# main-stm-03_1.net
KiCad netlist of a schematic drawn in EAGLE
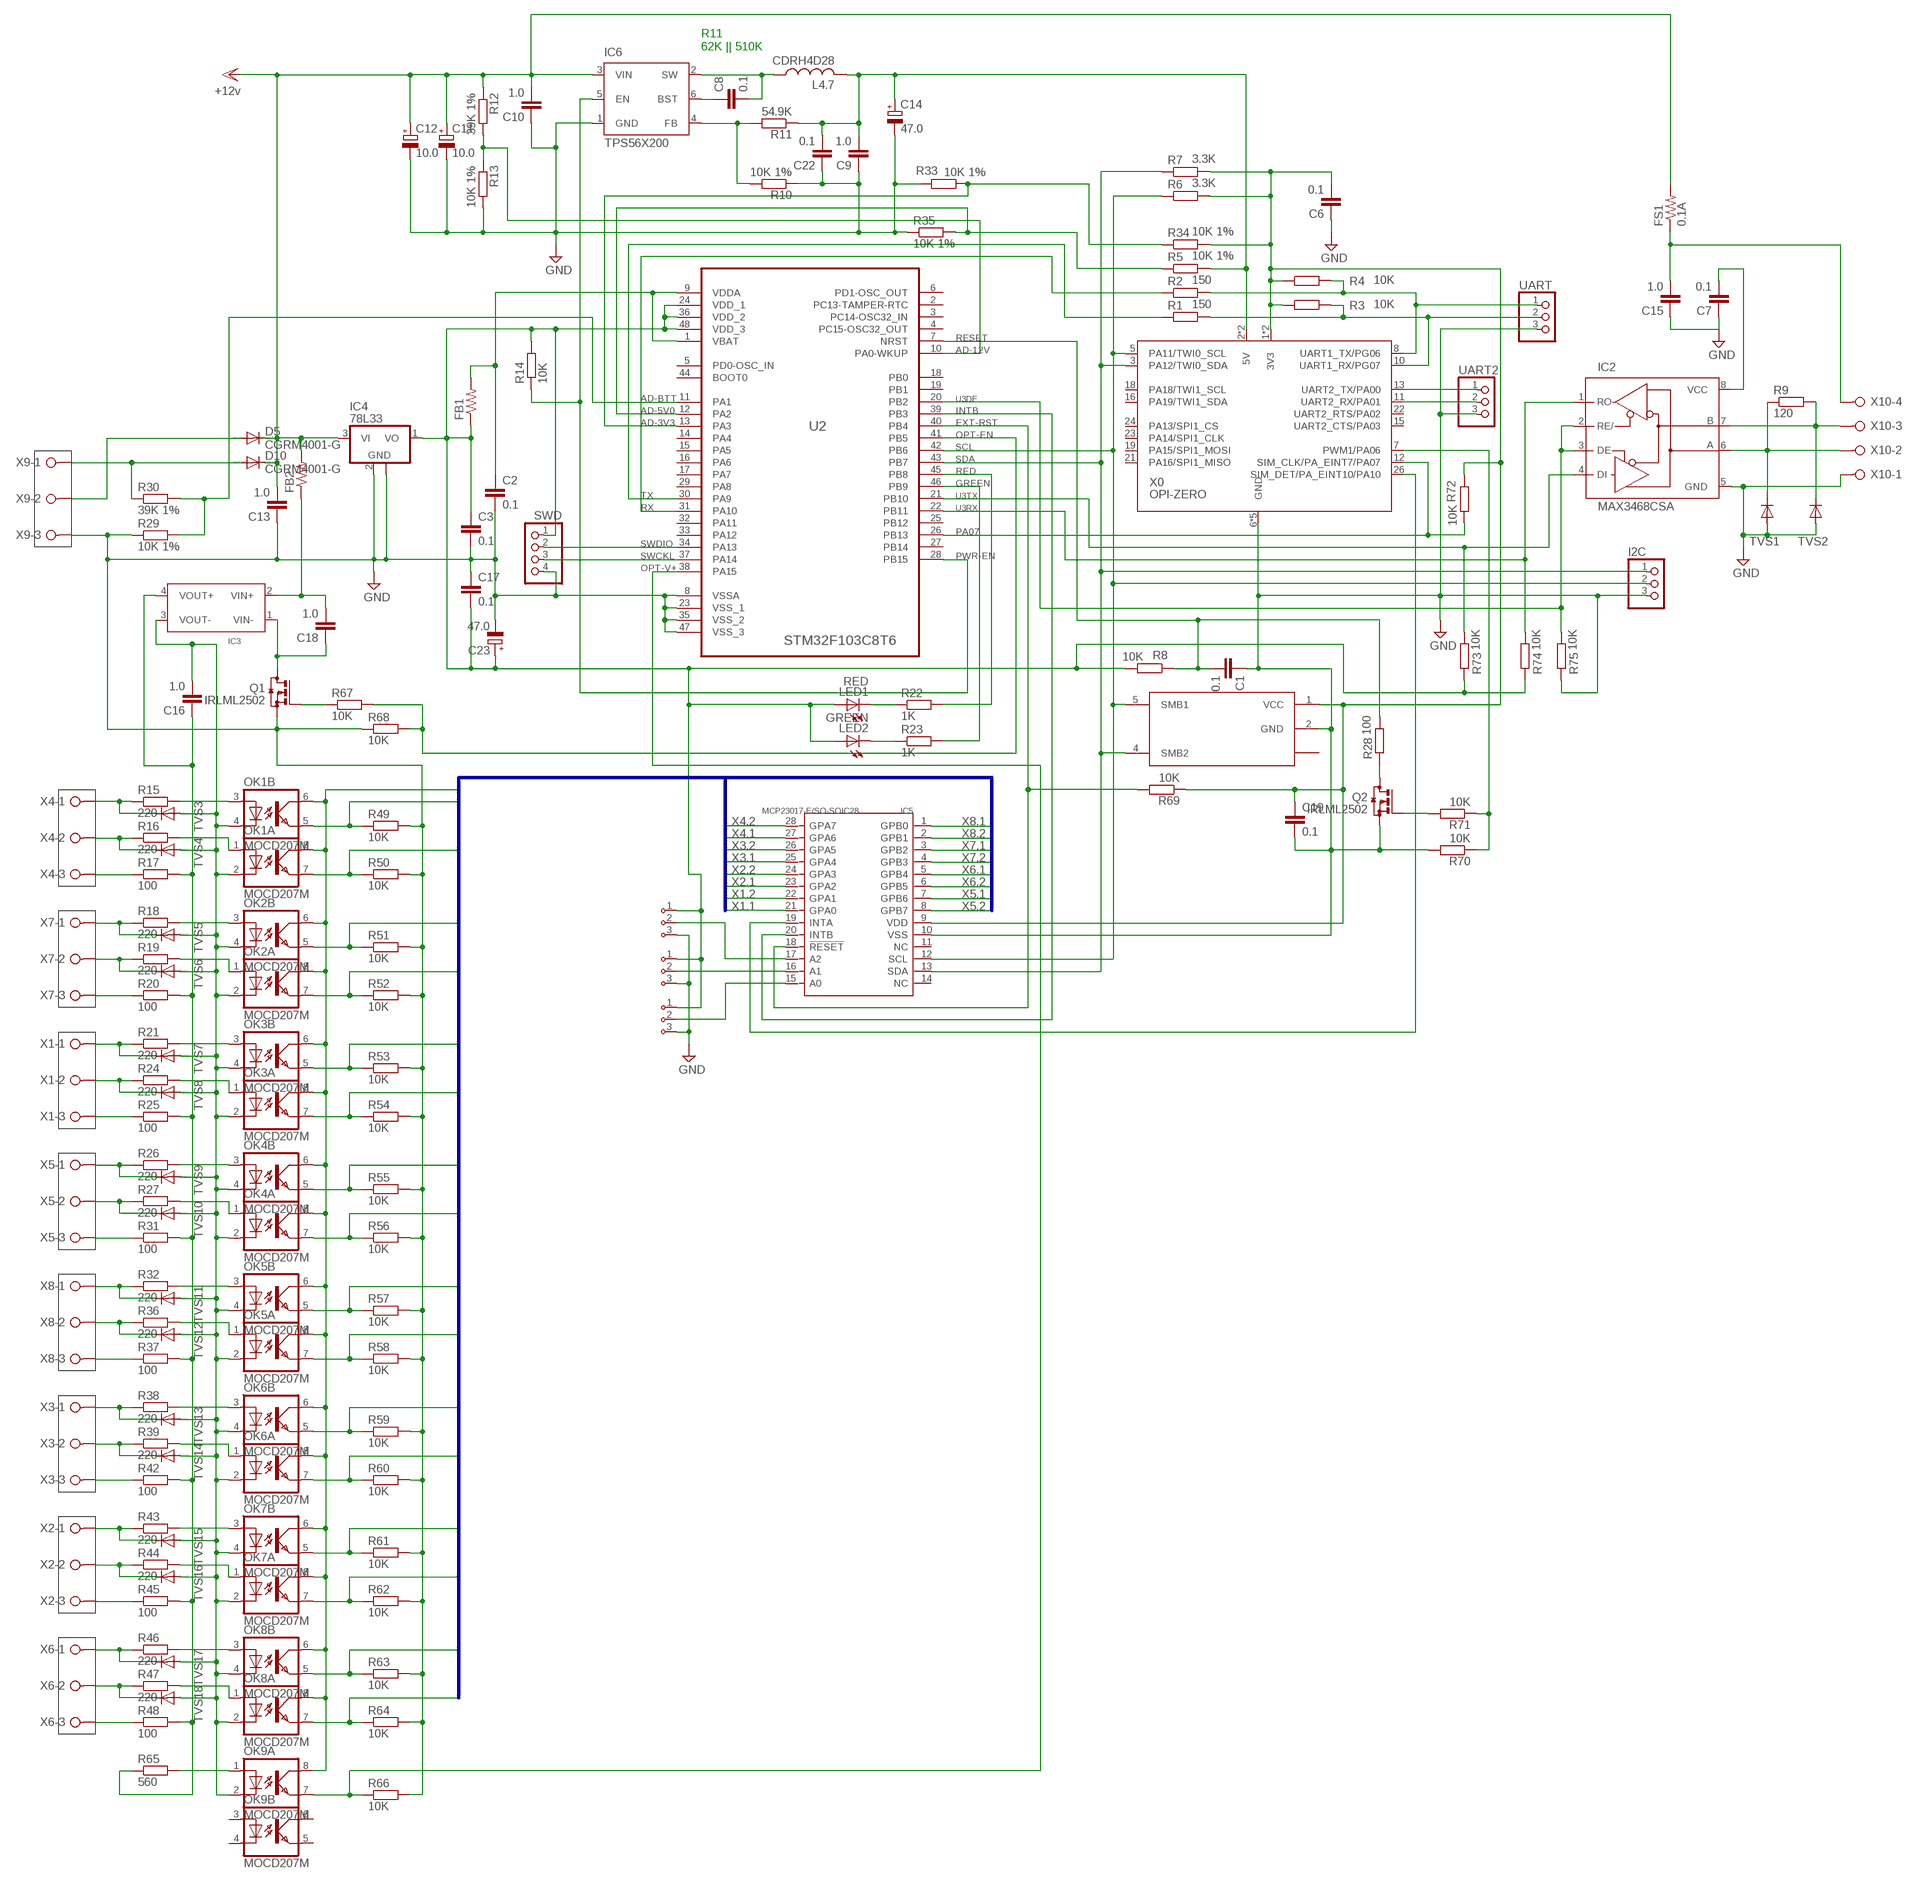
[diagram p0: schematic, sheet 1]

(export (version "E")
  (design (tool "Eeschema 10.0.6"))
  (components
    (comp (ref "A0")
      (value "ADDR3PIN0603")
      (footprint "eagle-import:0603-3PIN")
      (libsource (lib "eagle-import") (part "ADDR3PIN0603"))
    )
    (comp (ref "A1")
      (value "ADDR3PIN0603")
      (footprint "eagle-import:0603-3PIN")
      (libsource (lib "eagle-import") (part "ADDR3PIN0603"))
    )
    (comp (ref "A2")
      (value "ADDR3PIN0603")
      (footprint "eagle-import:0603-3PIN")
      (libsource (lib "eagle-import") (part "ADDR3PIN0603"))
    )
    (comp (ref "C1")
      (value "0.1")
      (footprint "eagle-import:C0603")
      (libsource (lib "eagle-import") (part "C-EUC0603"))
    )
    (comp (ref "C2")
      (value "0.1")
      (footprint "eagle-import:C0603")
      (libsource (lib "eagle-import") (part "C-EUC0603"))
    )
    (comp (ref "C3")
      (value "0.1")
      (footprint "eagle-import:C0603")
      (libsource (lib "eagle-import") (part "C-EUC0603"))
    )
    (comp (ref "C6")
      (value "0.1")
      (footprint "eagle-import:C0805")
      (libsource (lib "eagle-import") (part "C-EUC0805"))
    )
    (comp (ref "C7")
      (value "0.1")
      (footprint "eagle-import:C0805")
      (libsource (lib "eagle-import") (part "C-EUC0805"))
    )
    (comp (ref "C8")
      (value "0.1")
      (footprint "eagle-import:C0805")
      (libsource (lib "eagle-import") (part "C-EUC0805"))
    )
    (comp (ref "C9")
      (value "1.0")
      (footprint "eagle-import:C0805")
      (libsource (lib "eagle-import") (part "C-EUC0805"))
    )
    (comp (ref "C10")
      (value "1.0")
      (footprint "eagle-import:C1206")
      (libsource (lib "eagle-import") (part "C-EUC1206"))
    )
    (comp (ref "C11")
      (value "10.0")
      (footprint "eagle-import:C_6032-28R")
      (libsource (lib "eagle-import") (part "CPOL-EUC/6032-28R"))
    )
    (comp (ref "C12")
      (value "10.0")
      (footprint "eagle-import:C_6032-28R")
      (libsource (lib "eagle-import") (part "CPOL-EUC/6032-28R"))
    )
    (comp (ref "C13")
      (value "1.0")
      (footprint "eagle-import:C1206")
      (libsource (lib "eagle-import") (part "C-EUC1206"))
    )
    (comp (ref "C14")
      (value "47.0")
      (footprint "eagle-import:B_3528-21R")
      (libsource (lib "eagle-import") (part "CPOL-EUB/3528-21R"))
    )
    (comp (ref "C15")
      (value "1.0")
      (footprint "eagle-import:C1206")
      (libsource (lib "eagle-import") (part "C-EUC1206"))
    )
    (comp (ref "C16")
      (value "1.0")
      (footprint "eagle-import:C1206")
      (libsource (lib "eagle-import") (part "C-EUC1206"))
    )
    (comp (ref "C17")
      (value "0.1")
      (footprint "eagle-import:C0603")
      (libsource (lib "eagle-import") (part "C-EUC0603"))
    )
    (comp (ref "C18")
      (value "1.0")
      (footprint "eagle-import:C1206")
      (libsource (lib "eagle-import") (part "C-EUC1206"))
    )
    (comp (ref "C19")
      (value "0.1")
      (footprint "eagle-import:C0603")
      (libsource (lib "eagle-import") (part "C-EUC0603"))
    )
    (comp (ref "C22")
      (value "0.1")
      (footprint "eagle-import:C0805")
      (libsource (lib "eagle-import") (part "C-EUC0805"))
    )
    (comp (ref "C23")
      (value "47.0")
      (footprint "eagle-import:B_3528-21R")
      (libsource (lib "eagle-import") (part "CPOL-EUB/3528-21R"))
    )
    (comp (ref "D5")
      (value "CGRM4001-G")
      (footprint "eagle-import:SOD-123_MINI-SMA")
      (libsource (lib "eagle-import") (part "CGRM400-G1"))
    )
    (comp (ref "D10")
      (value "CGRM4001-G")
      (footprint "eagle-import:SOD-123_MINI-SMA")
      (libsource (lib "eagle-import") (part "CGRM400-G1"))
    )
    (comp (ref "FB1")
      (value "R-US_R0805")
      (footprint "eagle-import:R0805")
      (libsource (lib "eagle-import") (part "R-US_R0805"))
    )
    (comp (ref "FB2")
      (value "R-US_R1206")
      (footprint "eagle-import:R1206")
      (libsource (lib "eagle-import") (part "R-US_R1206"))
    )
    (comp (ref "FS1")
      (value "0.1A")
      (footprint "eagle-import:R1210")
      (libsource (lib "eagle-import") (part "R-US_R1210"))
    )
    (comp (ref "I2C")
      (value "PINHD-1X3")
      (footprint "eagle-import:1X03")
      (libsource (lib "eagle-import") (part "PINHD-1X3"))
    )
    (comp (ref "IC2")
      (value "MAX3468CSA")
      (footprint "eagle-import:SO08")
      (fields (field (name "MPN") "MAX3468CSA+"))
      (libsource (lib "eagle-import") (part "MAX34SA68C"))
    )
    (comp (ref "IC3")
      (value "DC-DC-CONV-4PIN-ISOLATINGMURATA-NME-05-12-SERIES")
      (footprint "eagle-import:DC-DC-MURATA-NME-05-12-SERIES")
      (libsource (lib "eagle-import") (part "DC-DC-CONV-4PIN-ISOLATINGMURATA-NME-05-12-SERIES"))
    )
    (comp (ref "IC4")
      (value "78L33")
      (footprint "eagle-import:SOT89")
      (libsource (lib "eagle-import") (part "78LF05"))
    )
    (comp (ref "IC5")
      (value "MCP23017-E/SO-SOIC28")
      (footprint "eagle-import:SOIC28-1.27-17.9X7.5MM")
      (fields (field (name "MPN") "MCP23017-E/SO"))
      (libsource (lib "eagle-import") (part "INTERFACE-MCP23017-E(SOIC28)"))
    )
    (comp (ref "IC6")
      (value "TPS56X200")
      (footprint "eagle-import:TSOT23-6_DDC")
      (libsource (lib "eagle-import") (part "TPS56X200"))
    )
    (comp (ref "IC7")
      (value "LTC1694")
      (footprint "eagle-import:SOT23-5")
      (libsource (lib "eagle-import") (part "LTC1694"))
    )
    (comp (ref "L4.7")
      (value "CDRH4D28")
      (footprint "eagle-import:CDRH4D28")
      (libsource (lib "eagle-import") (part "CDRH4D28"))
    )
    (comp (ref "LED1")
      (value "RED")
      (footprint "eagle-import:CHIPLED_1206")
      (libsource (lib "eagle-import") (part "LEDCHIPLED_1206"))
    )
    (comp (ref "LED2")
      (value "GREEN")
      (footprint "eagle-import:CHIPLED_1206")
      (libsource (lib "eagle-import") (part "LEDCHIPLED_1206"))
    )
    (comp (ref "OK1")
      (value "MOCD207M")
      (footprint "eagle-import:SOIC08-FAIRCHILD")
      (fields (field (name "MF") "FAIRCHILD SEMICONDUCTOR") (field (name "MPN") "MOCD207-M"))
      (libsource (lib "eagle-import") (part "MOCD20M7"))
    )
    (comp (ref "OK2")
      (value "MOCD207M")
      (footprint "eagle-import:SOIC08-FAIRCHILD")
      (fields (field (name "MF") "FAIRCHILD SEMICONDUCTOR") (field (name "MPN") "MOCD207-M"))
      (libsource (lib "eagle-import") (part "MOCD20M7"))
    )
    (comp (ref "OK3")
      (value "MOCD207M")
      (footprint "eagle-import:SOIC08-FAIRCHILD")
      (fields (field (name "MF") "FAIRCHILD SEMICONDUCTOR") (field (name "MPN") "MOCD207-M"))
      (libsource (lib "eagle-import") (part "MOCD20M7"))
    )
    (comp (ref "OK4")
      (value "MOCD207M")
      (footprint "eagle-import:SOIC08-FAIRCHILD")
      (fields (field (name "MF") "FAIRCHILD SEMICONDUCTOR") (field (name "MPN") "MOCD207-M"))
      (libsource (lib "eagle-import") (part "MOCD20M7"))
    )
    (comp (ref "OK5")
      (value "MOCD207M")
      (footprint "eagle-import:SOIC08-FAIRCHILD")
      (fields (field (name "MF") "FAIRCHILD SEMICONDUCTOR") (field (name "MPN") "MOCD207-M"))
      (libsource (lib "eagle-import") (part "MOCD20M7"))
    )
    (comp (ref "OK6")
      (value "MOCD207M")
      (footprint "eagle-import:SOIC08-FAIRCHILD")
      (fields (field (name "MF") "FAIRCHILD SEMICONDUCTOR") (field (name "MPN") "MOCD207-M"))
      (libsource (lib "eagle-import") (part "MOCD20M7"))
    )
    (comp (ref "OK7")
      (value "MOCD207M")
      (footprint "eagle-import:SOIC08-FAIRCHILD")
      (fields (field (name "MF") "FAIRCHILD SEMICONDUCTOR") (field (name "MPN") "MOCD207-M"))
      (libsource (lib "eagle-import") (part "MOCD20M7"))
    )
    (comp (ref "OK8")
      (value "MOCD207M")
      (footprint "eagle-import:SOIC08-FAIRCHILD")
      (fields (field (name "MF") "FAIRCHILD SEMICONDUCTOR") (field (name "MPN") "MOCD207-M"))
      (libsource (lib "eagle-import") (part "MOCD20M7"))
    )
    (comp (ref "OK9")
      (value "MOCD207M")
      (footprint "eagle-import:SOIC08-FAIRCHILD")
      (fields (field (name "MF") "FAIRCHILD SEMICONDUCTOR") (field (name "MPN") "MOCD207-M"))
      (libsource (lib "eagle-import") (part "MOCD20M7"))
    )
    (comp (ref "Q1")
      (value "IRLML2502")
      (footprint "eagle-import:SOT23")
      (libsource (lib "eagle-import") (part "IRLML2502"))
    )
    (comp (ref "Q2")
      (value "IRLML2502")
      (footprint "eagle-import:SOT23")
      (libsource (lib "eagle-import") (part "IRLML2502"))
    )
    (comp (ref "R1")
      (value "150")
      (footprint "eagle-import:R0603")
      (libsource (lib "eagle-import") (part "R-EU_R0603"))
    )
    (comp (ref "R2")
      (value "150")
      (footprint "eagle-import:R0603")
      (libsource (lib "eagle-import") (part "R-EU_R0603"))
    )
    (comp (ref "R3")
      (value "10K")
      (footprint "eagle-import:R0603")
      (libsource (lib "eagle-import") (part "R-EU_R0603"))
    )
    (comp (ref "R4")
      (value "10K")
      (footprint "eagle-import:R0603")
      (libsource (lib "eagle-import") (part "R-EU_R0603"))
    )
    (comp (ref "R5")
      (value "10K 1%")
      (footprint "eagle-import:R0603")
      (libsource (lib "eagle-import") (part "R-EU_R0603"))
    )
    (comp (ref "R6")
      (value "3.3K")
      (footprint "eagle-import:R0603")
      (libsource (lib "eagle-import") (part "R-EU_R0603"))
    )
    (comp (ref "R7")
      (value "3.3K")
      (footprint "eagle-import:R0603")
      (libsource (lib "eagle-import") (part "R-EU_R0603"))
    )
    (comp (ref "R8")
      (value "10K")
      (footprint "eagle-import:R0603")
      (libsource (lib "eagle-import") (part "R-EU_R0603"))
    )
    (comp (ref "R9")
      (value "120")
      (footprint "eagle-import:R1206")
      (libsource (lib "eagle-import") (part "R-EU_R1206"))
    )
    (comp (ref "R10")
      (value "10K 1%")
      (footprint "eagle-import:R0603")
      (libsource (lib "eagle-import") (part "R-EU_R0603"))
    )
    (comp (ref "R11")
      (value "54.9K")
      (footprint "eagle-import:R0603")
      (libsource (lib "eagle-import") (part "R-EU_R0603"))
    )
    (comp (ref "R12")
      (value "39K 1%")
      (footprint "eagle-import:R0603")
      (libsource (lib "eagle-import") (part "R-EU_R0603"))
    )
    (comp (ref "R13")
      (value "10K 1%")
      (footprint "eagle-import:R0603")
      (libsource (lib "eagle-import") (part "R-EU_R0603"))
    )
    (comp (ref "R14")
      (value "10K")
      (footprint "eagle-import:R0603")
      (libsource (lib "eagle-import") (part "R-EU_R0603"))
    )
    (comp (ref "R15")
      (value "220")
      (footprint "eagle-import:R0603")
      (libsource (lib "eagle-import") (part "R-EU_R0603"))
    )
    (comp (ref "R16")
      (value "220")
      (footprint "eagle-import:R0603")
      (libsource (lib "eagle-import") (part "R-EU_R0603"))
    )
    (comp (ref "R17")
      (value "100")
      (footprint "eagle-import:R0603")
      (libsource (lib "eagle-import") (part "R-EU_R0603"))
    )
    (comp (ref "R18")
      (value "220")
      (footprint "eagle-import:R0603")
      (libsource (lib "eagle-import") (part "R-EU_R0603"))
    )
    (comp (ref "R19")
      (value "220")
      (footprint "eagle-import:R0603")
      (libsource (lib "eagle-import") (part "R-EU_R0603"))
    )
    (comp (ref "R20")
      (value "100")
      (footprint "eagle-import:R0603")
      (libsource (lib "eagle-import") (part "R-EU_R0603"))
    )
    (comp (ref "R21")
      (value "220")
      (footprint "eagle-import:R0603")
      (libsource (lib "eagle-import") (part "R-EU_R0603"))
    )
    (comp (ref "R22")
      (value "1K")
      (footprint "eagle-import:R0603")
      (libsource (lib "eagle-import") (part "R-EU_R0603"))
    )
    (comp (ref "R23")
      (value "1K")
      (footprint "eagle-import:R0603")
      (libsource (lib "eagle-import") (part "R-EU_R0603"))
    )
    (comp (ref "R24")
      (value "220")
      (footprint "eagle-import:R0603")
      (libsource (lib "eagle-import") (part "R-EU_R0603"))
    )
    (comp (ref "R25")
      (value "100")
      (footprint "eagle-import:R0603")
      (libsource (lib "eagle-import") (part "R-EU_R0603"))
    )
    (comp (ref "R26")
      (value "220")
      (footprint "eagle-import:R0603")
      (libsource (lib "eagle-import") (part "R-EU_R0603"))
    )
    (comp (ref "R27")
      (value "220")
      (footprint "eagle-import:R0603")
      (libsource (lib "eagle-import") (part "R-EU_R0603"))
    )
    (comp (ref "R28")
      (value "100")
      (footprint "eagle-import:R0603")
      (libsource (lib "eagle-import") (part "R-EU_R0603"))
    )
    (comp (ref "R29")
      (value "10K 1%")
      (footprint "eagle-import:R0603")
      (libsource (lib "eagle-import") (part "R-EU_R0603"))
    )
    (comp (ref "R30")
      (value "39K 1%")
      (footprint "eagle-import:R0603")
      (libsource (lib "eagle-import") (part "R-EU_R0603"))
    )
    (comp (ref "R31")
      (value "100")
      (footprint "eagle-import:R0603")
      (libsource (lib "eagle-import") (part "R-EU_R0603"))
    )
    (comp (ref "R32")
      (value "220")
      (footprint "eagle-import:R0603")
      (libsource (lib "eagle-import") (part "R-EU_R0603"))
    )
    (comp (ref "R33")
      (value "10K 1%")
      (footprint "eagle-import:R0603")
      (libsource (lib "eagle-import") (part "R-EU_R0603"))
    )
    (comp (ref "R34")
      (value "10K 1%")
      (footprint "eagle-import:R0603")
      (libsource (lib "eagle-import") (part "R-EU_R0603"))
    )
    (comp (ref "R35")
      (value "10K 1%")
      (footprint "eagle-import:R0603")
      (libsource (lib "eagle-import") (part "R-EU_R0603"))
    )
    (comp (ref "R36")
      (value "220")
      (footprint "eagle-import:R0603")
      (libsource (lib "eagle-import") (part "R-EU_R0603"))
    )
    (comp (ref "R37")
      (value "100")
      (footprint "eagle-import:R0603")
      (libsource (lib "eagle-import") (part "R-EU_R0603"))
    )
    (comp (ref "R38")
      (value "220")
      (footprint "eagle-import:R0603")
      (libsource (lib "eagle-import") (part "R-EU_R0603"))
    )
    (comp (ref "R39")
      (value "220")
      (footprint "eagle-import:R0603")
      (libsource (lib "eagle-import") (part "R-EU_R0603"))
    )
    (comp (ref "R42")
      (value "100")
      (footprint "eagle-import:R0603")
      (libsource (lib "eagle-import") (part "R-EU_R0603"))
    )
    (comp (ref "R43")
      (value "220")
      (footprint "eagle-import:R0603")
      (libsource (lib "eagle-import") (part "R-EU_R0603"))
    )
    (comp (ref "R44")
      (value "220")
      (footprint "eagle-import:R0603")
      (libsource (lib "eagle-import") (part "R-EU_R0603"))
    )
    (comp (ref "R45")
      (value "100")
      (footprint "eagle-import:R0603")
      (libsource (lib "eagle-import") (part "R-EU_R0603"))
    )
    (comp (ref "R46")
      (value "220")
      (footprint "eagle-import:R0603")
      (libsource (lib "eagle-import") (part "R-EU_R0603"))
    )
    (comp (ref "R47")
      (value "220")
      (footprint "eagle-import:R0603")
      (libsource (lib "eagle-import") (part "R-EU_R0603"))
    )
    (comp (ref "R48")
      (value "100")
      (footprint "eagle-import:R0603")
      (libsource (lib "eagle-import") (part "R-EU_R0603"))
    )
    (comp (ref "R49")
      (value "10K")
      (footprint "eagle-import:R0603")
      (libsource (lib "eagle-import") (part "R-EU_R0603"))
    )
    (comp (ref "R50")
      (value "10K")
      (footprint "eagle-import:R0603")
      (libsource (lib "eagle-import") (part "R-EU_R0603"))
    )
    (comp (ref "R51")
      (value "10K")
      (footprint "eagle-import:R0603")
      (libsource (lib "eagle-import") (part "R-EU_R0603"))
    )
    (comp (ref "R52")
      (value "10K")
      (footprint "eagle-import:R0603")
      (libsource (lib "eagle-import") (part "R-EU_R0603"))
    )
    (comp (ref "R53")
      (value "10K")
      (footprint "eagle-import:R0603")
      (libsource (lib "eagle-import") (part "R-EU_R0603"))
    )
    (comp (ref "R54")
      (value "10K")
      (footprint "eagle-import:R0603")
      (libsource (lib "eagle-import") (part "R-EU_R0603"))
    )
    (comp (ref "R55")
      (value "10K")
      (footprint "eagle-import:R0603")
      (libsource (lib "eagle-import") (part "R-EU_R0603"))
    )
    (comp (ref "R56")
      (value "10K")
      (footprint "eagle-import:R0603")
      (libsource (lib "eagle-import") (part "R-EU_R0603"))
    )
    (comp (ref "R57")
      (value "10K")
      (footprint "eagle-import:R0603")
      (libsource (lib "eagle-import") (part "R-EU_R0603"))
    )
    (comp (ref "R58")
      (value "10K")
      (footprint "eagle-import:R0603")
      (libsource (lib "eagle-import") (part "R-EU_R0603"))
    )
    (comp (ref "R59")
      (value "10K")
      (footprint "eagle-import:R0603")
      (libsource (lib "eagle-import") (part "R-EU_R0603"))
    )
    (comp (ref "R60")
      (value "10K")
      (footprint "eagle-import:R0603")
      (libsource (lib "eagle-import") (part "R-EU_R0603"))
    )
    (comp (ref "R61")
      (value "10K")
      (footprint "eagle-import:R0603")
      (libsource (lib "eagle-import") (part "R-EU_R0603"))
    )
    (comp (ref "R62")
      (value "10K")
      (footprint "eagle-import:R0603")
      (libsource (lib "eagle-import") (part "R-EU_R0603"))
    )
    (comp (ref "R63")
      (value "10K")
      (footprint "eagle-import:R0603")
      (libsource (lib "eagle-import") (part "R-EU_R0603"))
    )
    (comp (ref "R64")
      (value "10K")
      (footprint "eagle-import:R0603")
      (libsource (lib "eagle-import") (part "R-EU_R0603"))
    )
    (comp (ref "R65")
      (value "560")
      (footprint "eagle-import:R0603")
      (libsource (lib "eagle-import") (part "R-EU_R0603"))
    )
    (comp (ref "R66")
      (value "10K")
      (footprint "eagle-import:R0603")
      (libsource (lib "eagle-import") (part "R-EU_R0603"))
    )
    (comp (ref "R67")
      (value "10K")
      (footprint "eagle-import:R0603")
      (libsource (lib "eagle-import") (part "R-EU_R0603"))
    )
    (comp (ref "R68")
      (value "10K")
      (footprint "eagle-import:R0603")
      (libsource (lib "eagle-import") (part "R-EU_R0603"))
    )
    (comp (ref "R69")
      (value "10K")
      (footprint "eagle-import:R0603")
      (libsource (lib "eagle-import") (part "R-EU_R0603"))
    )
    (comp (ref "R70")
      (value "10K")
      (footprint "eagle-import:R0603")
      (libsource (lib "eagle-import") (part "R-EU_R0603"))
    )
    (comp (ref "R71")
      (value "10K")
      (footprint "eagle-import:R0603")
      (libsource (lib "eagle-import") (part "R-EU_R0603"))
    )
    (comp (ref "R72")
      (value "10K")
      (footprint "eagle-import:R0603")
      (libsource (lib "eagle-import") (part "R-EU_R0603"))
    )
    (comp (ref "R73")
      (value "10K")
      (footprint "eagle-import:R0603")
      (libsource (lib "eagle-import") (part "R-EU_R0603"))
    )
    (comp (ref "R74")
      (value "10K")
      (footprint "eagle-import:R0603")
      (libsource (lib "eagle-import") (part "R-EU_R0603"))
    )
    (comp (ref "R75")
      (value "10K")
      (footprint "eagle-import:R0603")
      (libsource (lib "eagle-import") (part "R-EU_R0603"))
    )
    (comp (ref "SWD")
      (value "PINHD-1X4")
      (footprint "eagle-import:1X04")
      (libsource (lib "eagle-import") (part "PINHD-1X4"))
    )
    (comp (ref "TVS1")
      (value "DIODE-SOD323-W")
      (footprint "eagle-import:SOD323-W")
      (libsource (lib "eagle-import") (part "DIODE-SOD323-W"))
    )
    (comp (ref "TVS2")
      (value "DIODE-SOD323-W")
      (footprint "eagle-import:SOD323-W")
      (libsource (lib "eagle-import") (part "DIODE-SOD323-W"))
    )
    (comp (ref "TVS3")
      (value "DIODE-SOD323-W")
      (footprint "eagle-import:SOD323-W")
      (libsource (lib "eagle-import") (part "DIODE-SOD323-W"))
    )
    (comp (ref "TVS4")
      (value "DIODE-SOD323-W")
      (footprint "eagle-import:SOD323-W")
      (libsource (lib "eagle-import") (part "DIODE-SOD323-W"))
    )
    (comp (ref "TVS5")
      (value "DIODE-SOD323-W")
      (footprint "eagle-import:SOD323-W")
      (libsource (lib "eagle-import") (part "DIODE-SOD323-W"))
    )
    (comp (ref "TVS6")
      (value "DIODE-SOD323-W")
      (footprint "eagle-import:SOD323-W")
      (libsource (lib "eagle-import") (part "DIODE-SOD323-W"))
    )
    (comp (ref "TVS7")
      (value "DIODE-SOD323-W")
      (footprint "eagle-import:SOD323-W")
      (libsource (lib "eagle-import") (part "DIODE-SOD323-W"))
    )
    (comp (ref "TVS8")
      (value "DIODE-SOD323-W")
      (footprint "eagle-import:SOD323-W")
      (libsource (lib "eagle-import") (part "DIODE-SOD323-W"))
    )
    (comp (ref "TVS9")
      (value "DIODE-SOD323-W")
      (footprint "eagle-import:SOD323-W")
      (libsource (lib "eagle-import") (part "DIODE-SOD323-W"))
    )
    (comp (ref "TVS10")
      (value "DIODE-SOD323-W")
      (footprint "eagle-import:SOD323-W")
      (libsource (lib "eagle-import") (part "DIODE-SOD323-W"))
    )
    (comp (ref "TVS11")
      (value "DIODE-SOD323-W")
      (footprint "eagle-import:SOD323-W")
      (libsource (lib "eagle-import") (part "DIODE-SOD323-W"))
    )
    (comp (ref "TVS12")
      (value "DIODE-SOD323-W")
      (footprint "eagle-import:SOD323-W")
      (libsource (lib "eagle-import") (part "DIODE-SOD323-W"))
    )
    (comp (ref "TVS13")
      (value "DIODE-SOD323-W")
      (footprint "eagle-import:SOD323-W")
      (libsource (lib "eagle-import") (part "DIODE-SOD323-W"))
    )
    (comp (ref "TVS14")
      (value "DIODE-SOD323-W")
      (footprint "eagle-import:SOD323-W")
      (libsource (lib "eagle-import") (part "DIODE-SOD323-W"))
    )
    (comp (ref "TVS15")
      (value "DIODE-SOD323-W")
      (footprint "eagle-import:SOD323-W")
      (libsource (lib "eagle-import") (part "DIODE-SOD323-W"))
    )
    (comp (ref "TVS16")
      (value "DIODE-SOD323-W")
      (footprint "eagle-import:SOD323-W")
      (libsource (lib "eagle-import") (part "DIODE-SOD323-W"))
    )
    (comp (ref "TVS17")
      (value "DIODE-SOD323-W")
      (footprint "eagle-import:SOD323-W")
      (libsource (lib "eagle-import") (part "DIODE-SOD323-W"))
    )
    (comp (ref "TVS18")
      (value "DIODE-SOD323-W")
      (footprint "eagle-import:SOD323-W")
      (libsource (lib "eagle-import") (part "DIODE-SOD323-W"))
    )
    (comp (ref "U2")
      (value "STM32F103C8T6")
      (footprint "eagle-import:QFP50P900X900X160-48N")
      (fields (field (name "MPN") "STM32F100CBT6B"))
      (libsource (lib "eagle-import") (part "STM32F100CBT6B"))
    )
    (comp (ref "UART")
      (value "PINHD-1X3")
      (footprint "eagle-import:1X03")
      (libsource (lib "eagle-import") (part "PINHD-1X3"))
    )
    (comp (ref "UART2")
      (value "PINHD-1X3")
      (footprint "eagle-import:1X03")
      (libsource (lib "eagle-import") (part "PINHD-1X3"))
    )
    (comp (ref "X0")
      (value "OPI-ZERO")
      (footprint "eagle-import:OPI0")
      (libsource (lib "eagle-import") (part "OPI-ZERO"))
    )
    (comp (ref "X1")
      (value "W237-03P")
      (footprint "eagle-import:W237-133")
      (libsource (lib "eagle-import") (part "W237-03P"))
    )
    (comp (ref "X2")
      (value "W237-03P")
      (footprint "eagle-import:W237-133")
      (libsource (lib "eagle-import") (part "W237-03P"))
    )
    (comp (ref "X3")
      (value "W237-03P")
      (footprint "eagle-import:W237-133")
      (libsource (lib "eagle-import") (part "W237-03P"))
    )
    (comp (ref "X4")
      (value "W237-03P")
      (footprint "eagle-import:W237-133")
      (libsource (lib "eagle-import") (part "W237-03P"))
    )
    (comp (ref "X5")
      (value "W237-03P")
      (footprint "eagle-import:W237-133")
      (libsource (lib "eagle-import") (part "W237-03P"))
    )
    (comp (ref "X6")
      (value "W237-03P")
      (footprint "eagle-import:W237-133")
      (libsource (lib "eagle-import") (part "W237-03P"))
    )
    (comp (ref "X7")
      (value "W237-03P")
      (footprint "eagle-import:W237-133")
      (libsource (lib "eagle-import") (part "W237-03P"))
    )
    (comp (ref "X8")
      (value "W237-03P")
      (footprint "eagle-import:W237-133")
      (libsource (lib "eagle-import") (part "W237-03P"))
    )
    (comp (ref "X9")
      (value "W237-03P")
      (footprint "eagle-import:W237-133")
      (libsource (lib "eagle-import") (part "W237-03P"))
    )
    (comp (ref "X10")
      (value "W237-04P")
      (footprint "eagle-import:W237-4P")
      (libsource (lib "eagle-import") (part "W237-04P"))
    )
  )
  (nets
    (net (code "1") (name "+12v") (class "Default")
      (node (ref "C10") (pin "2") (pinfunction "2_2") (pintype "passive"))
      (node (ref "C11") (pin "+") (pinfunction "+_+") (pintype "passive"))
      (node (ref "C12") (pin "+") (pinfunction "+_+") (pintype "passive"))
      (node (ref "C13") (pin "2") (pinfunction "2_2") (pintype "passive"))
      (node (ref "D10") (pin "C") (pinfunction "C_C") (pintype "passive"))
      (node (ref "D5") (pin "C") (pinfunction "C_C") (pintype "passive"))
      (node (ref "FB2") (pin "2") (pinfunction "2_2") (pintype "passive"))
      (node (ref "FS1") (pin "2") (pinfunction "2_2") (pintype "passive"))
      (node (ref "IC4") (pin "3") (pinfunction "VI_3") (pintype "input"))
      (node (ref "IC6") (pin "3") (pinfunction "VIN_3") (pintype "input"))
      (node (ref "R12") (pin "1") (pinfunction "1_1") (pintype "passive"))
    )
    (net (code "2") (name "/AD-3V3") (class "Default")
      (node (ref "R33") (pin "1") (pinfunction "1_1") (pintype "passive"))
      (node (ref "R34") (pin "1") (pinfunction "1_1") (pintype "passive"))
      (node (ref "U2") (pin "13") (pinfunction "PA3_13") (pintype "bidirectional"))
    )
    (net (code "3") (name "/AD-5V0") (class "Default")
      (node (ref "R35") (pin "2") (pinfunction "2_2") (pintype "passive"))
      (node (ref "R5") (pin "1") (pinfunction "1_1") (pintype "passive"))
      (node (ref "U2") (pin "12") (pinfunction "PA2_12") (pintype "bidirectional"))
    )
    (net (code "4") (name "/AD-12V") (class "Default")
      (node (ref "R12") (pin "2") (pinfunction "2_2") (pintype "passive"))
      (node (ref "R13") (pin "1") (pinfunction "1_1") (pintype "passive"))
      (node (ref "U2") (pin "10") (pinfunction "PA0-WKUP_10") (pintype "bidirectional"))
    )
    (net (code "5") (name "/AD-BTT") (class "Default")
      (node (ref "R29") (pin "2") (pinfunction "2_2") (pintype "passive"))
      (node (ref "R30") (pin "2") (pinfunction "2_2") (pintype "passive"))
      (node (ref "U2") (pin "11") (pinfunction "PA1_11") (pintype "bidirectional"))
    )
    (net (code "6") (name "/EXT-RST") (class "Default")
      (node (ref "IC5") (pin "18") (pinfunction "~{RESET}_18") (pintype "bidirectional"))
      (node (ref "R69") (pin "2") (pinfunction "2_2") (pintype "passive"))
      (node (ref "U2") (pin "40") (pinfunction "PB4_40") (pintype "bidirectional"))
    )
    (net (code "7") (name "/GREEN") (class "Default")
      (node (ref "R23") (pin "2") (pinfunction "2_2") (pintype "passive"))
      (node (ref "U2") (pin "46") (pinfunction "PB9_46") (pintype "bidirectional"))
    )
    (net (code "8") (name "/INTB") (class "Default")
      (node (ref "IC5") (pin "20") (pinfunction "INTB_20") (pintype "bidirectional"))
      (node (ref "U2") (pin "39") (pinfunction "PB3_39") (pintype "bidirectional"))
    )
    (net (code "9") (name "/OPT-EN") (class "Default")
      (node (ref "R67") (pin "2") (pinfunction "2_2") (pintype "passive"))
      (node (ref "R68") (pin "2") (pinfunction "2_2") (pintype "passive"))
      (node (ref "U2") (pin "41") (pinfunction "PB5_41") (pintype "bidirectional"))
    )
    (net (code "10") (name "/OPT-V+") (class "Default")
      (node (ref "OK9") (pin "7") (pinfunction "EMIT_7") (pintype "passive"))
      (node (ref "R66") (pin "1") (pinfunction "1_1") (pintype "passive"))
      (node (ref "U2") (pin "38") (pinfunction "PA15_38") (pintype "bidirectional"))
    )
    (net (code "11") (name "/PA07") (class "Default")
      (node (ref "R72") (pin "2") (pinfunction "2_2") (pintype "passive"))
      (node (ref "U2") (pin "26") (pinfunction "PB13_26") (pintype "bidirectional"))
      (node (ref "X0") (pin "12") (pinfunction "SIM_CLK/PA_EINT7/PA07_12") (pintype "bidirectional"))
    )
    (net (code "12") (name "/PWR-EN") (class "Default")
      (node (ref "IC6") (pin "5") (pinfunction "EN_5") (pintype "input"))
      (node (ref "R14") (pin "1") (pinfunction "1_1") (pintype "passive"))
      (node (ref "U2") (pin "28") (pinfunction "PB15_28") (pintype "bidirectional"))
    )
    (net (code "13") (name "/RED") (class "Default")
      (node (ref "R22") (pin "2") (pinfunction "2_2") (pintype "passive"))
      (node (ref "U2") (pin "45") (pinfunction "PB8_45") (pintype "bidirectional"))
    )
    (net (code "14") (name "/RESET") (class "Default")
      (node (ref "C1") (pin "2") (pinfunction "2_2") (pintype "passive"))
      (node (ref "R28") (pin "2") (pinfunction "2_2") (pintype "passive"))
      (node (ref "R8") (pin "1") (pinfunction "1_1") (pintype "passive"))
      (node (ref "U2") (pin "7") (pinfunction "NRST_7") (pintype "bidirectional"))
    )
    (net (code "15") (name "/RX") (class "Default")
      (node (ref "R2") (pin "1") (pinfunction "1_1") (pintype "passive"))
      (node (ref "U2") (pin "31") (pinfunction "PA10_31") (pintype "bidirectional"))
    )
    (net (code "16") (name "/SCL") (class "Default")
      (node (ref "I2C") (pin "2") (pinfunction "2_2") (pintype "passive"))
      (node (ref "IC5") (pin "12") (pinfunction "SCL_12") (pintype "bidirectional"))
      (node (ref "IC7") (pin "5") (pinfunction "SMB1_5") (pintype "bidirectional"))
      (node (ref "R6") (pin "1") (pinfunction "1_1") (pintype "passive"))
      (node (ref "U2") (pin "42") (pinfunction "PB6_42") (pintype "bidirectional"))
      (node (ref "X0") (pin "5") (pinfunction "PA11/TWI0_SCL_5") (pintype "bidirectional"))
    )
    (net (code "17") (name "/SDA") (class "Default")
      (node (ref "I2C") (pin "1") (pinfunction "1_1") (pintype "passive"))
      (node (ref "IC5") (pin "13") (pinfunction "SDA_13") (pintype "bidirectional"))
      (node (ref "IC7") (pin "4") (pinfunction "SMB2_4") (pintype "bidirectional"))
      (node (ref "R7") (pin "1") (pinfunction "1_1") (pintype "passive"))
      (node (ref "U2") (pin "43") (pinfunction "PB7_43") (pintype "bidirectional"))
      (node (ref "X0") (pin "3") (pinfunction "PA12/TWI0_SDA_3") (pintype "bidirectional"))
    )
    (net (code "18") (name "/SWCKL") (class "Default")
      (node (ref "SWD") (pin "3") (pinfunction "3_3") (pintype "passive"))
      (node (ref "U2") (pin "37") (pinfunction "PA14_37") (pintype "bidirectional"))
    )
    (net (code "19") (name "/SWDIO") (class "Default")
      (node (ref "SWD") (pin "2") (pinfunction "2_2") (pintype "passive"))
      (node (ref "U2") (pin "34") (pinfunction "PA13_34") (pintype "bidirectional"))
    )
    (net (code "20") (name "/TX") (class "Default")
      (node (ref "R1") (pin "1") (pinfunction "1_1") (pintype "passive"))
      (node (ref "U2") (pin "30") (pinfunction "PA9_30") (pintype "bidirectional"))
    )
    (net (code "21") (name "/U3DE") (class "Default")
      (node (ref "IC2") (pin "2") (pinfunction "RE/_2") (pintype "input"))
      (node (ref "IC2") (pin "3") (pinfunction "DE_3") (pintype "input"))
      (node (ref "R75") (pin "2") (pinfunction "2_2") (pintype "passive"))
      (node (ref "U2") (pin "20") (pinfunction "PB2_20") (pintype "bidirectional"))
    )
    (net (code "22") (name "/U3RX") (class "Default")
      (node (ref "IC2") (pin "1") (pinfunction "RO_1") (pintype "output"))
      (node (ref "R74") (pin "2") (pinfunction "2_2") (pintype "passive"))
      (node (ref "U2") (pin "22") (pinfunction "PB11_22") (pintype "bidirectional"))
    )
    (net (code "23") (name "/U3TX") (class "Default")
      (node (ref "IC2") (pin "4") (pinfunction "DI_4") (pintype "input"))
      (node (ref "R73") (pin "2") (pinfunction "2_2") (pintype "passive"))
      (node (ref "U2") (pin "21") (pinfunction "PB10_21") (pintype "bidirectional"))
    )
    (net (code "24") (name "/VCC") (class "Default")
      (node (ref "A0") (pin "1") (pinfunction "P$2_1") (pintype "power_in"))
      (node (ref "A1") (pin "1") (pinfunction "P$2_1") (pintype "power_in"))
      (node (ref "A2") (pin "1") (pinfunction "P$2_1") (pintype "power_in"))
      (node (ref "C17") (pin "2") (pinfunction "2_2") (pintype "passive"))
      (node (ref "C23") (pin "+") (pinfunction "+_+") (pintype "passive"))
      (node (ref "C3") (pin "1") (pinfunction "1_1") (pintype "passive"))
      (node (ref "C7") (pin "2") (pinfunction "2_2") (pintype "passive"))
      (node (ref "FB1") (pin "1") (pinfunction "1_1") (pintype "passive"))
      (node (ref "IC2") (pin "8") (pinfunction "VCC_8") (pintype "power_in"))
      (node (ref "IC4") (pin "1") (pinfunction "VO_1") (pintype "passive"))
      (node (ref "LED1") (pin "A") (pinfunction "A_A") (pintype "passive"))
      (node (ref "LED2") (pin "A") (pinfunction "A_A") (pintype "passive"))
      (node (ref "R14") (pin "2") (pinfunction "2_2") (pintype "passive"))
      (node (ref "R73") (pin "1") (pinfunction "1_1") (pintype "passive"))
      (node (ref "R74") (pin "1") (pinfunction "1_1") (pintype "passive"))
      (node (ref "R8") (pin "2") (pinfunction "2_2") (pintype "passive"))
      (node (ref "SWD") (pin "1") (pinfunction "1_1") (pintype "passive"))
      (node (ref "U2") (pin "24") (pinfunction "VDD_1_24") (pintype "power_in"))
      (node (ref "U2") (pin "36") (pinfunction "VDD_2_36") (pintype "power_in"))
      (node (ref "U2") (pin "48") (pinfunction "VDD_3_48") (pintype "power_in"))
    )
    (net (code "25") (name "/X1.1") (class "Default")
      (node (ref "IC5") (pin "21") (pinfunction "GPA0_21") (pintype "bidirectional"))
      (node (ref "OK3") (pin "5") (pinfunction "EMIT_5") (pintype "passive"))
      (node (ref "R53") (pin "1") (pinfunction "1_1") (pintype "passive"))
    )
    (net (code "26") (name "/X1.2") (class "Default")
      (node (ref "IC5") (pin "22") (pinfunction "GPA1_22") (pintype "bidirectional"))
      (node (ref "OK3") (pin "7") (pinfunction "EMIT_7") (pintype "passive"))
      (node (ref "R54") (pin "1") (pinfunction "1_1") (pintype "passive"))
    )
    (net (code "27") (name "/X2.1") (class "Default")
      (node (ref "IC5") (pin "23") (pinfunction "GPA2_23") (pintype "bidirectional"))
      (node (ref "OK7") (pin "5") (pinfunction "EMIT_5") (pintype "passive"))
      (node (ref "R61") (pin "1") (pinfunction "1_1") (pintype "passive"))
    )
    (net (code "28") (name "/X2.2") (class "Default")
      (node (ref "IC5") (pin "24") (pinfunction "GPA3_24") (pintype "bidirectional"))
      (node (ref "OK7") (pin "7") (pinfunction "EMIT_7") (pintype "passive"))
      (node (ref "R62") (pin "1") (pinfunction "1_1") (pintype "passive"))
    )
    (net (code "29") (name "/X3.1") (class "Default")
      (node (ref "IC5") (pin "25") (pinfunction "GPA4_25") (pintype "bidirectional"))
      (node (ref "OK6") (pin "5") (pinfunction "EMIT_5") (pintype "passive"))
      (node (ref "R59") (pin "1") (pinfunction "1_1") (pintype "passive"))
    )
    (net (code "30") (name "/X3.2") (class "Default")
      (node (ref "IC5") (pin "26") (pinfunction "GPA5_26") (pintype "bidirectional"))
      (node (ref "OK6") (pin "7") (pinfunction "EMIT_7") (pintype "passive"))
      (node (ref "R60") (pin "1") (pinfunction "1_1") (pintype "passive"))
    )
    (net (code "31") (name "/X4.1") (class "Default")
      (node (ref "IC5") (pin "27") (pinfunction "GPA6_27") (pintype "bidirectional"))
      (node (ref "OK1") (pin "5") (pinfunction "EMIT_5") (pintype "passive"))
      (node (ref "R49") (pin "1") (pinfunction "1_1") (pintype "passive"))
    )
    (net (code "32") (name "/X4.2") (class "Default")
      (node (ref "IC5") (pin "28") (pinfunction "GPA7_28") (pintype "bidirectional"))
      (node (ref "OK1") (pin "7") (pinfunction "EMIT_7") (pintype "passive"))
      (node (ref "R50") (pin "1") (pinfunction "1_1") (pintype "passive"))
    )
    (net (code "33") (name "/X5.1") (class "Default")
      (node (ref "IC5") (pin "7") (pinfunction "GPB6_7") (pintype "bidirectional"))
      (node (ref "OK4") (pin "5") (pinfunction "EMIT_5") (pintype "passive"))
      (node (ref "R55") (pin "1") (pinfunction "1_1") (pintype "passive"))
    )
    (net (code "34") (name "/X5.2") (class "Default")
      (node (ref "IC5") (pin "8") (pinfunction "GPB7_8") (pintype "bidirectional"))
      (node (ref "OK4") (pin "7") (pinfunction "EMIT_7") (pintype "passive"))
      (node (ref "R56") (pin "1") (pinfunction "1_1") (pintype "passive"))
    )
    (net (code "35") (name "/X6.1") (class "Default")
      (node (ref "IC5") (pin "5") (pinfunction "GPB4_5") (pintype "bidirectional"))
      (node (ref "OK8") (pin "5") (pinfunction "EMIT_5") (pintype "passive"))
      (node (ref "R63") (pin "1") (pinfunction "1_1") (pintype "passive"))
    )
    (net (code "36") (name "/X6.2") (class "Default")
      (node (ref "IC5") (pin "6") (pinfunction "GPB5_6") (pintype "bidirectional"))
      (node (ref "OK8") (pin "7") (pinfunction "EMIT_7") (pintype "passive"))
      (node (ref "R64") (pin "1") (pinfunction "1_1") (pintype "passive"))
    )
    (net (code "37") (name "/X7.1") (class "Default")
      (node (ref "IC5") (pin "3") (pinfunction "GPB2_3") (pintype "bidirectional"))
      (node (ref "OK2") (pin "5") (pinfunction "EMIT_5") (pintype "passive"))
      (node (ref "R51") (pin "1") (pinfunction "1_1") (pintype "passive"))
    )
    (net (code "38") (name "/X7.2") (class "Default")
      (node (ref "IC5") (pin "4") (pinfunction "GPB3_4") (pintype "bidirectional"))
      (node (ref "OK2") (pin "7") (pinfunction "EMIT_7") (pintype "passive"))
      (node (ref "R52") (pin "1") (pinfunction "1_1") (pintype "passive"))
    )
    (net (code "39") (name "/X8.1") (class "Default")
      (node (ref "IC5") (pin "1") (pinfunction "GPB0_1") (pintype "bidirectional"))
      (node (ref "OK5") (pin "5") (pinfunction "EMIT_5") (pintype "passive"))
      (node (ref "R57") (pin "1") (pinfunction "1_1") (pintype "passive"))
    )
    (net (code "40") (name "/X8.2") (class "Default")
      (node (ref "IC5") (pin "2") (pinfunction "GPB1_2") (pintype "bidirectional"))
      (node (ref "OK5") (pin "7") (pinfunction "EMIT_7") (pintype "passive"))
      (node (ref "R58") (pin "1") (pinfunction "1_1") (pintype "passive"))
    )
    (net (code "41") (name "/Z3V3") (class "Default")
      (node (ref "C19") (pin "1") (pinfunction "1_1") (pintype "passive"))
      (node (ref "C6") (pin "2") (pinfunction "2_2") (pintype "passive"))
      (node (ref "IC5") (pin "9") (pinfunction "VDD_9") (pintype "bidirectional"))
      (node (ref "IC7") (pin "1") (pinfunction "VCC_1") (pintype "power_in"))
      (node (ref "OK1") (pin "6") (pinfunction "COL_6") (pintype "passive"))
      (node (ref "OK1") (pin "8") (pinfunction "COL_8") (pintype "passive"))
      (node (ref "OK2") (pin "6") (pinfunction "COL_6") (pintype "passive"))
      (node (ref "OK2") (pin "8") (pinfunction "COL_8") (pintype "passive"))
      (node (ref "OK3") (pin "6") (pinfunction "COL_6") (pintype "passive"))
      (node (ref "OK3") (pin "8") (pinfunction "COL_8") (pintype "passive"))
      (node (ref "OK4") (pin "6") (pinfunction "COL_6") (pintype "passive"))
      (node (ref "OK4") (pin "8") (pinfunction "COL_8") (pintype "passive"))
      (node (ref "OK5") (pin "6") (pinfunction "COL_6") (pintype "passive"))
      (node (ref "OK5") (pin "8") (pinfunction "COL_8") (pintype "passive"))
      (node (ref "OK6") (pin "6") (pinfunction "COL_6") (pintype "passive"))
      (node (ref "OK6") (pin "8") (pinfunction "COL_8") (pintype "passive"))
      (node (ref "OK7") (pin "6") (pinfunction "COL_6") (pintype "passive"))
      (node (ref "OK7") (pin "8") (pinfunction "COL_8") (pintype "passive"))
      (node (ref "OK8") (pin "6") (pinfunction "COL_6") (pintype "passive"))
      (node (ref "OK8") (pin "8") (pinfunction "COL_8") (pintype "passive"))
      (node (ref "OK9") (pin "8") (pinfunction "COL_8") (pintype "passive"))
      (node (ref "R3") (pin "1") (pinfunction "1_1") (pintype "passive"))
      (node (ref "R34") (pin "2") (pinfunction "2_2") (pintype "passive"))
      (node (ref "R4") (pin "1") (pinfunction "1_1") (pintype "passive"))
      (node (ref "R6") (pin "2") (pinfunction "2_2") (pintype "passive"))
      (node (ref "R69") (pin "1") (pinfunction "1_1") (pintype "passive"))
      (node (ref "R7") (pin "2") (pinfunction "2_2") (pintype "passive"))
      (node (ref "R72") (pin "1") (pinfunction "1_1") (pintype "passive"))
      (node (ref "X0") (pin "1") (pinfunction "3V3_1") (pintype "power_in"))
      (node (ref "X0") (pin "17") (pinfunction "3V3_17") (pintype "power_in"))
    )
    (net (code "42") (name "GND") (class "Default")
      (node (ref "A0") (pin "3") (pinfunction "P$3_3") (pintype "power_in"))
      (node (ref "A1") (pin "3") (pinfunction "P$3_3") (pintype "power_in"))
      (node (ref "A2") (pin "3") (pinfunction "P$3_3") (pintype "power_in"))
      (node (ref "C1") (pin "1") (pinfunction "1_1") (pintype "passive"))
      (node (ref "C10") (pin "1") (pinfunction "1_1") (pintype "passive"))
      (node (ref "C11") (pin "-") (pinfunction "-_-") (pintype "passive"))
      (node (ref "C12") (pin "-") (pinfunction "-_-") (pintype "passive"))
      (node (ref "C13") (pin "1") (pinfunction "1_1") (pintype "passive"))
      (node (ref "C14") (pin "-") (pinfunction "-_-") (pintype "passive"))
      (node (ref "C15") (pin "1") (pinfunction "1_1") (pintype "passive"))
      (node (ref "C17") (pin "1") (pinfunction "1_1") (pintype "passive"))
      (node (ref "C19") (pin "2") (pinfunction "2_2") (pintype "passive"))
      (node (ref "C2") (pin "2") (pinfunction "2_2") (pintype "passive"))
      (node (ref "C22") (pin "1") (pinfunction "1_1") (pintype "passive"))
      (node (ref "C23") (pin "-") (pinfunction "-_-") (pintype "passive"))
      (node (ref "C3") (pin "2") (pinfunction "2_2") (pintype "passive"))
      (node (ref "C6") (pin "1") (pinfunction "1_1") (pintype "passive"))
      (node (ref "C7") (pin "1") (pinfunction "1_1") (pintype "passive"))
      (node (ref "C9") (pin "1") (pinfunction "1_1") (pintype "passive"))
      (node (ref "I2C") (pin "3") (pinfunction "3_3") (pintype "passive"))
      (node (ref "IC2") (pin "5") (pinfunction "GND_5") (pintype "power_in"))
      (node (ref "IC4") (pin "2") (pinfunction "GND_2") (pintype "passive"))
      (node (ref "IC4") (pin "2@1") (pinfunction "GND_2@1") (pintype "passive"))
      (node (ref "IC5") (pin "10") (pinfunction "VSS_10") (pintype "bidirectional"))
      (node (ref "IC6") (pin "1") (pinfunction "GND_1") (pintype "power_in"))
      (node (ref "IC7") (pin "2") (pinfunction "GND_2") (pintype "power_in"))
      (node (ref "Q1") (pin "2") (pinfunction "S_2") (pintype "passive"))
      (node (ref "Q2") (pin "2") (pinfunction "S_2") (pintype "passive"))
      (node (ref "R10") (pin "1") (pinfunction "1_1") (pintype "passive"))
      (node (ref "R13") (pin "2") (pinfunction "2_2") (pintype "passive"))
      (node (ref "R29") (pin "1") (pinfunction "1_1") (pintype "passive"))
      (node (ref "R33") (pin "2") (pinfunction "2_2") (pintype "passive"))
      (node (ref "R35") (pin "1") (pinfunction "1_1") (pintype "passive"))
      (node (ref "R49") (pin "2") (pinfunction "2_2") (pintype "passive"))
      (node (ref "R50") (pin "2") (pinfunction "2_2") (pintype "passive"))
      (node (ref "R51") (pin "2") (pinfunction "2_2") (pintype "passive"))
      (node (ref "R52") (pin "2") (pinfunction "2_2") (pintype "passive"))
      (node (ref "R53") (pin "2") (pinfunction "2_2") (pintype "passive"))
      (node (ref "R54") (pin "2") (pinfunction "2_2") (pintype "passive"))
      (node (ref "R55") (pin "2") (pinfunction "2_2") (pintype "passive"))
      (node (ref "R56") (pin "2") (pinfunction "2_2") (pintype "passive"))
      (node (ref "R57") (pin "2") (pinfunction "2_2") (pintype "passive"))
      (node (ref "R58") (pin "2") (pinfunction "2_2") (pintype "passive"))
      (node (ref "R59") (pin "2") (pinfunction "2_2") (pintype "passive"))
      (node (ref "R60") (pin "2") (pinfunction "2_2") (pintype "passive"))
      (node (ref "R61") (pin "2") (pinfunction "2_2") (pintype "passive"))
      (node (ref "R62") (pin "2") (pinfunction "2_2") (pintype "passive"))
      (node (ref "R63") (pin "2") (pinfunction "2_2") (pintype "passive"))
      (node (ref "R64") (pin "2") (pinfunction "2_2") (pintype "passive"))
      (node (ref "R66") (pin "2") (pinfunction "2_2") (pintype "passive"))
      (node (ref "R68") (pin "1") (pinfunction "1_1") (pintype "passive"))
      (node (ref "R70") (pin "2") (pinfunction "2_2") (pintype "passive"))
      (node (ref "R75") (pin "1") (pinfunction "1_1") (pintype "passive"))
      (node (ref "SWD") (pin "4") (pinfunction "4_4") (pintype "passive"))
      (node (ref "TVS1") (pin "A") (pinfunction "A_A") (pintype "passive"))
      (node (ref "TVS2") (pin "A") (pinfunction "A_A") (pintype "passive"))
      (node (ref "U2") (pin "23") (pinfunction "VSS_1_23") (pintype "power_in"))
      (node (ref "U2") (pin "35") (pinfunction "VSS_2_35") (pintype "power_in"))
      (node (ref "U2") (pin "47") (pinfunction "VSS_3_47") (pintype "power_in"))
      (node (ref "U2") (pin "8") (pinfunction "VSSA_8") (pintype "power_in"))
      (node (ref "UART") (pin "3") (pinfunction "3_3") (pintype "passive"))
      (node (ref "UART2") (pin "3") (pinfunction "3_3") (pintype "passive"))
      (node (ref "X0") (pin "14") (pinfunction "GND_14") (pintype "power_in"))
      (node (ref "X0") (pin "20") (pinfunction "GND_20") (pintype "power_in"))
      (node (ref "X0") (pin "25") (pinfunction "GND_25") (pintype "power_in"))
      (node (ref "X0") (pin "6") (pinfunction "GND_6") (pintype "power_in"))
      (node (ref "X0") (pin "9") (pinfunction "GND_9") (pintype "power_in"))
      (node (ref "X10") (pin "1") (pinfunction "KL_1") (pintype "passive"))
      (node (ref "X9") (pin "3") (pinfunction "KL_3") (pintype "passive"))
    )
    (net (code "43") (name "Net-(A0-P$1)") (class "Default")
      (node (ref "A0") (pin "2") (pinfunction "P$1_2") (pintype "bidirectional"))
      (node (ref "IC5") (pin "15") (pinfunction "A0_15") (pintype "bidirectional"))
    )
    (net (code "44") (name "Net-(A1-P$1)") (class "Default")
      (node (ref "A1") (pin "2") (pinfunction "P$1_2") (pintype "bidirectional"))
      (node (ref "IC5") (pin "16") (pinfunction "A1_16") (pintype "bidirectional"))
    )
    (net (code "45") (name "Net-(A2-P$1)") (class "Default")
      (node (ref "A2") (pin "2") (pinfunction "P$1_2") (pintype "bidirectional"))
      (node (ref "IC5") (pin "17") (pinfunction "A2_17") (pintype "bidirectional"))
    )
    (net (code "46") (name "Net-(IC2-A)") (class "Default")
      (node (ref "IC2") (pin "6") (pinfunction "A_6") (pintype "passive"))
      (node (ref "R9") (pin "1") (pinfunction "1_1") (pintype "passive"))
      (node (ref "TVS1") (pin "C") (pinfunction "C_C") (pintype "passive"))
      (node (ref "X10") (pin "2") (pinfunction "KL_2") (pintype "passive"))
    )
    (net (code "47") (name "Net-(IC2-B)") (class "Default")
      (node (ref "IC2") (pin "7") (pinfunction "B_7") (pintype "passive"))
      (node (ref "R9") (pin "2") (pinfunction "2_2") (pintype "passive"))
      (node (ref "TVS2") (pin "C") (pinfunction "C_C") (pintype "passive"))
      (node (ref "X10") (pin "3") (pinfunction "KL_3") (pintype "passive"))
    )
    (net (code "48") (name "Net-(IC3-VIN+)") (class "Default")
      (node (ref "C18") (pin "2") (pinfunction "2_2") (pintype "passive"))
      (node (ref "FB2") (pin "1") (pinfunction "1_1") (pintype "passive"))
      (node (ref "IC3") (pin "2") (pinfunction "VIN+_2") (pintype "bidirectional"))
    )
    (net (code "49") (name "Net-(IC3-VIN-)") (class "Default")
      (node (ref "C18") (pin "1") (pinfunction "1_1") (pintype "passive"))
      (node (ref "IC3") (pin "1") (pinfunction "VIN-_1") (pintype "bidirectional"))
      (node (ref "Q1") (pin "3") (pinfunction "D_3") (pintype "passive"))
    )
    (net (code "50") (name "Net-(IC3-VOUT+)") (class "Default")
      (node (ref "C16") (pin "1") (pinfunction "1_1") (pintype "passive"))
      (node (ref "IC3") (pin "4") (pinfunction "VOUT+_4") (pintype "bidirectional"))
      (node (ref "R17") (pin "2") (pinfunction "2_2") (pintype "passive"))
      (node (ref "R20") (pin "2") (pinfunction "2_2") (pintype "passive"))
      (node (ref "R25") (pin "2") (pinfunction "2_2") (pintype "passive"))
      (node (ref "R31") (pin "2") (pinfunction "2_2") (pintype "passive"))
      (node (ref "R37") (pin "2") (pinfunction "2_2") (pintype "passive"))
      (node (ref "R42") (pin "2") (pinfunction "2_2") (pintype "passive"))
      (node (ref "R45") (pin "2") (pinfunction "2_2") (pintype "passive"))
      (node (ref "R48") (pin "2") (pinfunction "2_2") (pintype "passive"))
      (node (ref "R65") (pin "1") (pinfunction "1_1") (pintype "passive"))
    )
    (net (code "51") (name "Net-(IC3-VOUT-)") (class "Default")
      (node (ref "C16") (pin "2") (pinfunction "2_2") (pintype "passive"))
      (node (ref "IC3") (pin "3") (pinfunction "VOUT-_3") (pintype "bidirectional"))
      (node (ref "OK1") (pin "2") (pinfunction "C_2") (pintype "passive"))
      (node (ref "OK1") (pin "4") (pinfunction "C_4") (pintype "passive"))
      (node (ref "OK2") (pin "2") (pinfunction "C_2") (pintype "passive"))
      (node (ref "OK2") (pin "4") (pinfunction "C_4") (pintype "passive"))
      (node (ref "OK3") (pin "2") (pinfunction "C_2") (pintype "passive"))
      (node (ref "OK3") (pin "4") (pinfunction "C_4") (pintype "passive"))
      (node (ref "OK4") (pin "2") (pinfunction "C_2") (pintype "passive"))
      (node (ref "OK4") (pin "4") (pinfunction "C_4") (pintype "passive"))
      (node (ref "OK5") (pin "2") (pinfunction "C_2") (pintype "passive"))
      (node (ref "OK5") (pin "4") (pinfunction "C_4") (pintype "passive"))
      (node (ref "OK6") (pin "2") (pinfunction "C_2") (pintype "passive"))
      (node (ref "OK6") (pin "4") (pinfunction "C_4") (pintype "passive"))
      (node (ref "OK7") (pin "2") (pinfunction "C_2") (pintype "passive"))
      (node (ref "OK7") (pin "4") (pinfunction "C_4") (pintype "passive"))
      (node (ref "OK8") (pin "2") (pinfunction "C_2") (pintype "passive"))
      (node (ref "OK8") (pin "4") (pinfunction "C_4") (pintype "passive"))
      (node (ref "OK9") (pin "2") (pinfunction "C_2") (pintype "passive"))
      (node (ref "TVS10") (pin "A") (pinfunction "A_A") (pintype "passive"))
      (node (ref "TVS11") (pin "A") (pinfunction "A_A") (pintype "passive"))
      (node (ref "TVS12") (pin "A") (pinfunction "A_A") (pintype "passive"))
      (node (ref "TVS13") (pin "A") (pinfunction "A_A") (pintype "passive"))
      (node (ref "TVS14") (pin "A") (pinfunction "A_A") (pintype "passive"))
      (node (ref "TVS15") (pin "A") (pinfunction "A_A") (pintype "passive"))
      (node (ref "TVS16") (pin "A") (pinfunction "A_A") (pintype "passive"))
      (node (ref "TVS17") (pin "A") (pinfunction "A_A") (pintype "passive"))
      (node (ref "TVS18") (pin "A") (pinfunction "A_A") (pintype "passive"))
      (node (ref "TVS3") (pin "A") (pinfunction "A_A") (pintype "passive"))
      (node (ref "TVS4") (pin "A") (pinfunction "A_A") (pintype "passive"))
      (node (ref "TVS5") (pin "A") (pinfunction "A_A") (pintype "passive"))
      (node (ref "TVS6") (pin "A") (pinfunction "A_A") (pintype "passive"))
      (node (ref "TVS7") (pin "A") (pinfunction "A_A") (pintype "passive"))
      (node (ref "TVS8") (pin "A") (pinfunction "A_A") (pintype "passive"))
      (node (ref "TVS9") (pin "A") (pinfunction "A_A") (pintype "passive"))
    )
    (net (code "52") (name "Net-(IC5-INTA)") (class "Default")
      (node (ref "IC5") (pin "19") (pinfunction "INTA_19") (pintype "bidirectional"))
      (node (ref "X0") (pin "26") (pinfunction "SIM_DET/PA_EINT10/PA10_26") (pintype "bidirectional"))
    )
    (net (code "53") (name "Net-(IC6-BST)") (class "Default")
      (node (ref "C8") (pin "1") (pinfunction "1_1") (pintype "passive"))
      (node (ref "IC6") (pin "6") (pinfunction "BST_6") (pintype "input"))
    )
    (net (code "54") (name "Net-(IC6-FB)") (class "Default")
      (node (ref "IC6") (pin "4") (pinfunction "FB_4") (pintype "input"))
      (node (ref "R10") (pin "2") (pinfunction "2_2") (pintype "passive"))
      (node (ref "R11") (pin "2") (pinfunction "2_2") (pintype "passive"))
    )
    (net (code "55") (name "Net-(IC6-SW)") (class "Default")
      (node (ref "C8") (pin "2") (pinfunction "2_2") (pintype "passive"))
      (node (ref "IC6") (pin "2") (pinfunction "SW_2") (pintype "passive"))
      (node (ref "L4.7") (pin "P$1") (pinfunction "1_P$1") (pintype "passive"))
    )
    (net (code "56") (name "Net-(L4.7-2)") (class "Default")
      (node (ref "C14") (pin "+") (pinfunction "+_+") (pintype "passive"))
      (node (ref "C22") (pin "2") (pinfunction "2_2") (pintype "passive"))
      (node (ref "C9") (pin "2") (pinfunction "2_2") (pintype "passive"))
      (node (ref "L4.7") (pin "P$2") (pinfunction "2_P$2") (pintype "passive"))
      (node (ref "R11") (pin "1") (pinfunction "1_1") (pintype "passive"))
      (node (ref "R5") (pin "2") (pinfunction "2_2") (pintype "passive"))
      (node (ref "X0") (pin "2") (pinfunction "5V_2") (pintype "power_in"))
      (node (ref "X0") (pin "4") (pinfunction "5V_4") (pintype "power_in"))
    )
    (net (code "57") (name "Net-(LED1-PadC)") (class "Default")
      (node (ref "LED1") (pin "C") (pinfunction "C_C") (pintype "passive"))
      (node (ref "R22") (pin "1") (pinfunction "1_1") (pintype "passive"))
    )
    (net (code "58") (name "Net-(LED2-PadC)") (class "Default")
      (node (ref "LED2") (pin "C") (pinfunction "C_C") (pintype "passive"))
      (node (ref "R23") (pin "1") (pinfunction "1_1") (pintype "passive"))
    )
    (net (code "59") (name "Net-(OK1A-A)") (class "Default")
      (node (ref "OK1") (pin "1") (pinfunction "A_1") (pintype "passive"))
      (node (ref "R16") (pin "2") (pinfunction "2_2") (pintype "passive"))
    )
    (net (code "60") (name "Net-(OK1B-A)") (class "Default")
      (node (ref "OK1") (pin "3") (pinfunction "A_3") (pintype "passive"))
      (node (ref "R15") (pin "2") (pinfunction "2_2") (pintype "passive"))
    )
    (net (code "61") (name "Net-(OK2A-A)") (class "Default")
      (node (ref "OK2") (pin "1") (pinfunction "A_1") (pintype "passive"))
      (node (ref "R19") (pin "2") (pinfunction "2_2") (pintype "passive"))
    )
    (net (code "62") (name "Net-(OK2B-A)") (class "Default")
      (node (ref "OK2") (pin "3") (pinfunction "A_3") (pintype "passive"))
      (node (ref "R18") (pin "2") (pinfunction "2_2") (pintype "passive"))
    )
    (net (code "63") (name "Net-(OK3A-A)") (class "Default")
      (node (ref "OK3") (pin "1") (pinfunction "A_1") (pintype "passive"))
      (node (ref "R24") (pin "2") (pinfunction "2_2") (pintype "passive"))
    )
    (net (code "64") (name "Net-(OK3B-A)") (class "Default")
      (node (ref "OK3") (pin "3") (pinfunction "A_3") (pintype "passive"))
      (node (ref "R21") (pin "2") (pinfunction "2_2") (pintype "passive"))
    )
    (net (code "65") (name "Net-(OK4A-A)") (class "Default")
      (node (ref "OK4") (pin "1") (pinfunction "A_1") (pintype "passive"))
      (node (ref "R27") (pin "2") (pinfunction "2_2") (pintype "passive"))
    )
    (net (code "66") (name "Net-(OK4B-A)") (class "Default")
      (node (ref "OK4") (pin "3") (pinfunction "A_3") (pintype "passive"))
      (node (ref "R26") (pin "2") (pinfunction "2_2") (pintype "passive"))
    )
    (net (code "67") (name "Net-(OK5A-A)") (class "Default")
      (node (ref "OK5") (pin "1") (pinfunction "A_1") (pintype "passive"))
      (node (ref "R36") (pin "2") (pinfunction "2_2") (pintype "passive"))
    )
    (net (code "68") (name "Net-(OK5B-A)") (class "Default")
      (node (ref "OK5") (pin "3") (pinfunction "A_3") (pintype "passive"))
      (node (ref "R32") (pin "2") (pinfunction "2_2") (pintype "passive"))
    )
    (net (code "69") (name "Net-(OK6A-A)") (class "Default")
      (node (ref "OK6") (pin "1") (pinfunction "A_1") (pintype "passive"))
      (node (ref "R39") (pin "2") (pinfunction "2_2") (pintype "passive"))
    )
    (net (code "70") (name "Net-(OK6B-A)") (class "Default")
      (node (ref "OK6") (pin "3") (pinfunction "A_3") (pintype "passive"))
      (node (ref "R38") (pin "2") (pinfunction "2_2") (pintype "passive"))
    )
    (net (code "71") (name "Net-(OK7A-A)") (class "Default")
      (node (ref "OK7") (pin "1") (pinfunction "A_1") (pintype "passive"))
      (node (ref "R44") (pin "2") (pinfunction "2_2") (pintype "passive"))
    )
    (net (code "72") (name "Net-(OK7B-A)") (class "Default")
      (node (ref "OK7") (pin "3") (pinfunction "A_3") (pintype "passive"))
      (node (ref "R43") (pin "2") (pinfunction "2_2") (pintype "passive"))
    )
    (net (code "73") (name "Net-(OK8A-A)") (class "Default")
      (node (ref "OK8") (pin "1") (pinfunction "A_1") (pintype "passive"))
      (node (ref "R47") (pin "2") (pinfunction "2_2") (pintype "passive"))
    )
    (net (code "74") (name "Net-(OK8B-A)") (class "Default")
      (node (ref "OK8") (pin "3") (pinfunction "A_3") (pintype "passive"))
      (node (ref "R46") (pin "2") (pinfunction "2_2") (pintype "passive"))
    )
    (net (code "75") (name "Net-(OK9A-A)") (class "Default")
      (node (ref "OK9") (pin "1") (pinfunction "A_1") (pintype "passive"))
      (node (ref "R65") (pin "2") (pinfunction "2_2") (pintype "passive"))
    )
    (net (code "76") (name "Net-(Q1-G)") (class "Default")
      (node (ref "Q1") (pin "1") (pinfunction "G_1") (pintype "passive"))
      (node (ref "R67") (pin "1") (pinfunction "1_1") (pintype "passive"))
    )
    (net (code "77") (name "Net-(Q2-D)") (class "Default")
      (node (ref "Q2") (pin "3") (pinfunction "D_3") (pintype "passive"))
      (node (ref "R28") (pin "1") (pinfunction "1_1") (pintype "passive"))
    )
    (net (code "78") (name "Net-(Q2-G)") (class "Default")
      (node (ref "Q2") (pin "1") (pinfunction "G_1") (pintype "passive"))
      (node (ref "R71") (pin "2") (pinfunction "2_2") (pintype "passive"))
    )
    (net (code "79") (name "Net-(U2-VBAT)") (class "Default")
      (node (ref "C2") (pin "1") (pinfunction "1_1") (pintype "passive"))
      (node (ref "FB1") (pin "2") (pinfunction "2_2") (pintype "passive"))
      (node (ref "U2") (pin "1") (pinfunction "VBAT_1") (pintype "power_in"))
      (node (ref "U2") (pin "9") (pinfunction "VDDA_9") (pintype "power_in"))
    )
    (net (code "80") (name "Net-(X0-PWM1{slash}PA06)") (class "Default")
      (node (ref "R70") (pin "1") (pinfunction "1_1") (pintype "passive"))
      (node (ref "R71") (pin "1") (pinfunction "1_1") (pintype "passive"))
      (node (ref "X0") (pin "7") (pinfunction "PWM1/PA06_7") (pintype "bidirectional"))
    )
    (net (code "81") (name "Net-(X0-UART1_RX{slash}PG07)") (class "Default")
      (node (ref "R1") (pin "2") (pinfunction "2_2") (pintype "passive"))
      (node (ref "R3") (pin "2") (pinfunction "2_2") (pintype "passive"))
      (node (ref "UART") (pin "2") (pinfunction "2_2") (pintype "passive"))
      (node (ref "X0") (pin "10") (pinfunction "UART1_RX/PG07_10") (pintype "bidirectional"))
    )
    (net (code "82") (name "Net-(X0-UART1_TX{slash}PG06)") (class "Default")
      (node (ref "R2") (pin "2") (pinfunction "2_2") (pintype "passive"))
      (node (ref "R4") (pin "2") (pinfunction "2_2") (pintype "passive"))
      (node (ref "UART") (pin "1") (pinfunction "1_1") (pintype "passive"))
      (node (ref "X0") (pin "8") (pinfunction "UART1_TX/PG06_8") (pintype "bidirectional"))
    )
    (net (code "83") (name "Net-(X0-UART2_RX{slash}PA01)") (class "Default")
      (node (ref "UART2") (pin "2") (pinfunction "2_2") (pintype "passive"))
      (node (ref "X0") (pin "11") (pinfunction "UART2_RX/PA01_11") (pintype "bidirectional"))
    )
    (net (code "84") (name "Net-(X0-UART2_TX{slash}PA00)") (class "Default")
      (node (ref "UART2") (pin "1") (pinfunction "1_1") (pintype "passive"))
      (node (ref "X0") (pin "13") (pinfunction "UART2_TX/PA00_13") (pintype "bidirectional"))
    )
    (net (code "85") (name "Net-(X1A-KL)") (class "Default")
      (node (ref "R21") (pin "1") (pinfunction "1_1") (pintype "passive"))
      (node (ref "TVS7") (pin "C") (pinfunction "C_C") (pintype "passive"))
      (node (ref "X1") (pin "1") (pinfunction "KL_1") (pintype "passive"))
    )
    (net (code "86") (name "Net-(X1B-KL)") (class "Default")
      (node (ref "R24") (pin "1") (pinfunction "1_1") (pintype "passive"))
      (node (ref "TVS8") (pin "C") (pinfunction "C_C") (pintype "passive"))
      (node (ref "X1") (pin "2") (pinfunction "KL_2") (pintype "passive"))
    )
    (net (code "87") (name "Net-(X1C-KL)") (class "Default")
      (node (ref "R25") (pin "1") (pinfunction "1_1") (pintype "passive"))
      (node (ref "X1") (pin "3") (pinfunction "KL_3") (pintype "passive"))
    )
    (net (code "88") (name "Net-(X2A-KL)") (class "Default")
      (node (ref "R43") (pin "1") (pinfunction "1_1") (pintype "passive"))
      (node (ref "TVS15") (pin "C") (pinfunction "C_C") (pintype "passive"))
      (node (ref "X2") (pin "1") (pinfunction "KL_1") (pintype "passive"))
    )
    (net (code "89") (name "Net-(X2B-KL)") (class "Default")
      (node (ref "R44") (pin "1") (pinfunction "1_1") (pintype "passive"))
      (node (ref "TVS16") (pin "C") (pinfunction "C_C") (pintype "passive"))
      (node (ref "X2") (pin "2") (pinfunction "KL_2") (pintype "passive"))
    )
    (net (code "90") (name "Net-(X2C-KL)") (class "Default")
      (node (ref "R45") (pin "1") (pinfunction "1_1") (pintype "passive"))
      (node (ref "X2") (pin "3") (pinfunction "KL_3") (pintype "passive"))
    )
    (net (code "91") (name "Net-(X3A-KL)") (class "Default")
      (node (ref "R38") (pin "1") (pinfunction "1_1") (pintype "passive"))
      (node (ref "TVS13") (pin "C") (pinfunction "C_C") (pintype "passive"))
      (node (ref "X3") (pin "1") (pinfunction "KL_1") (pintype "passive"))
    )
    (net (code "92") (name "Net-(X3B-KL)") (class "Default")
      (node (ref "R39") (pin "1") (pinfunction "1_1") (pintype "passive"))
      (node (ref "TVS14") (pin "C") (pinfunction "C_C") (pintype "passive"))
      (node (ref "X3") (pin "2") (pinfunction "KL_2") (pintype "passive"))
    )
    (net (code "93") (name "Net-(X3C-KL)") (class "Default")
      (node (ref "R42") (pin "1") (pinfunction "1_1") (pintype "passive"))
      (node (ref "X3") (pin "3") (pinfunction "KL_3") (pintype "passive"))
    )
    (net (code "94") (name "Net-(X4A-KL)") (class "Default")
      (node (ref "R15") (pin "1") (pinfunction "1_1") (pintype "passive"))
      (node (ref "TVS3") (pin "C") (pinfunction "C_C") (pintype "passive"))
      (node (ref "X4") (pin "1") (pinfunction "KL_1") (pintype "passive"))
    )
    (net (code "95") (name "Net-(X4B-KL)") (class "Default")
      (node (ref "R16") (pin "1") (pinfunction "1_1") (pintype "passive"))
      (node (ref "TVS4") (pin "C") (pinfunction "C_C") (pintype "passive"))
      (node (ref "X4") (pin "2") (pinfunction "KL_2") (pintype "passive"))
    )
    (net (code "96") (name "Net-(X4C-KL)") (class "Default")
      (node (ref "R17") (pin "1") (pinfunction "1_1") (pintype "passive"))
      (node (ref "X4") (pin "3") (pinfunction "KL_3") (pintype "passive"))
    )
    (net (code "97") (name "Net-(X5A-KL)") (class "Default")
      (node (ref "R26") (pin "1") (pinfunction "1_1") (pintype "passive"))
      (node (ref "TVS9") (pin "C") (pinfunction "C_C") (pintype "passive"))
      (node (ref "X5") (pin "1") (pinfunction "KL_1") (pintype "passive"))
    )
    (net (code "98") (name "Net-(X5B-KL)") (class "Default")
      (node (ref "R27") (pin "1") (pinfunction "1_1") (pintype "passive"))
      (node (ref "TVS10") (pin "C") (pinfunction "C_C") (pintype "passive"))
      (node (ref "X5") (pin "2") (pinfunction "KL_2") (pintype "passive"))
    )
    (net (code "99") (name "Net-(X5C-KL)") (class "Default")
      (node (ref "R31") (pin "1") (pinfunction "1_1") (pintype "passive"))
      (node (ref "X5") (pin "3") (pinfunction "KL_3") (pintype "passive"))
    )
    (net (code "100") (name "Net-(X6A-KL)") (class "Default")
      (node (ref "R46") (pin "1") (pinfunction "1_1") (pintype "passive"))
      (node (ref "TVS17") (pin "C") (pinfunction "C_C") (pintype "passive"))
      (node (ref "X6") (pin "1") (pinfunction "KL_1") (pintype "passive"))
    )
    (net (code "101") (name "Net-(X6B-KL)") (class "Default")
      (node (ref "R47") (pin "1") (pinfunction "1_1") (pintype "passive"))
      (node (ref "TVS18") (pin "C") (pinfunction "C_C") (pintype "passive"))
      (node (ref "X6") (pin "2") (pinfunction "KL_2") (pintype "passive"))
    )
    (net (code "102") (name "Net-(X6C-KL)") (class "Default")
      (node (ref "R48") (pin "1") (pinfunction "1_1") (pintype "passive"))
      (node (ref "X6") (pin "3") (pinfunction "KL_3") (pintype "passive"))
    )
    (net (code "103") (name "Net-(X7A-KL)") (class "Default")
      (node (ref "R18") (pin "1") (pinfunction "1_1") (pintype "passive"))
      (node (ref "TVS5") (pin "C") (pinfunction "C_C") (pintype "passive"))
      (node (ref "X7") (pin "1") (pinfunction "KL_1") (pintype "passive"))
    )
    (net (code "104") (name "Net-(X7B-KL)") (class "Default")
      (node (ref "R19") (pin "1") (pinfunction "1_1") (pintype "passive"))
      (node (ref "TVS6") (pin "C") (pinfunction "C_C") (pintype "passive"))
      (node (ref "X7") (pin "2") (pinfunction "KL_2") (pintype "passive"))
    )
    (net (code "105") (name "Net-(X7C-KL)") (class "Default")
      (node (ref "R20") (pin "1") (pinfunction "1_1") (pintype "passive"))
      (node (ref "X7") (pin "3") (pinfunction "KL_3") (pintype "passive"))
    )
    (net (code "106") (name "Net-(X8A-KL)") (class "Default")
      (node (ref "R32") (pin "1") (pinfunction "1_1") (pintype "passive"))
      (node (ref "TVS11") (pin "C") (pinfunction "C_C") (pintype "passive"))
      (node (ref "X8") (pin "1") (pinfunction "KL_1") (pintype "passive"))
    )
    (net (code "107") (name "Net-(X8B-KL)") (class "Default")
      (node (ref "R36") (pin "1") (pinfunction "1_1") (pintype "passive"))
      (node (ref "TVS12") (pin "C") (pinfunction "C_C") (pintype "passive"))
      (node (ref "X8") (pin "2") (pinfunction "KL_2") (pintype "passive"))
    )
    (net (code "108") (name "Net-(X8C-KL)") (class "Default")
      (node (ref "R37") (pin "1") (pinfunction "1_1") (pintype "passive"))
      (node (ref "X8") (pin "3") (pinfunction "KL_3") (pintype "passive"))
    )
    (net (code "109") (name "Net-(X9A-KL)") (class "Default")
      (node (ref "D10") (pin "A") (pinfunction "A_A") (pintype "passive"))
      (node (ref "R30") (pin "1") (pinfunction "1_1") (pintype "passive"))
      (node (ref "X9") (pin "1") (pinfunction "KL_1") (pintype "passive"))
    )
    (net (code "110") (name "Net-(X9B-KL)") (class "Default")
      (node (ref "D5") (pin "A") (pinfunction "A_A") (pintype "passive"))
      (node (ref "X9") (pin "2") (pinfunction "KL_2") (pintype "passive"))
    )
    (net (code "111") (name "Net-(X10D-KL)") (class "Default")
      (node (ref "C15") (pin "2") (pinfunction "2_2") (pintype "passive"))
      (node (ref "FS1") (pin "1") (pinfunction "1_1") (pintype "passive"))
      (node (ref "X10") (pin "4") (pinfunction "KL_4") (pintype "passive"))
    )
    (net (code "112") (name "unconnected-(IC5-NC-Pad11)") (class "Default")
      (node (ref "IC5") (pin "11") (pinfunction "NC_11") (pintype "bidirectional"))
    )
    (net (code "113") (name "unconnected-(IC5-NC-Pad14)") (class "Default")
      (node (ref "IC5") (pin "14") (pinfunction "NC_14") (pintype "bidirectional"))
    )
    (net (code "114") (name "unconnected-(IC7-NC-Pad3)") (class "Default")
      (node (ref "IC7") (pin "3") (pinfunction "NC_3") (pintype "no_connect"))
    )
    (net (code "115") (name "unconnected-(OK9B-A-Pad3)") (class "Default")
      (node (ref "OK9") (pin "3") (pinfunction "A_3") (pintype "passive"))
    )
    (net (code "116") (name "unconnected-(OK9B-C-Pad4)") (class "Default")
      (node (ref "OK9") (pin "4") (pinfunction "C_4") (pintype "passive"))
    )
    (net (code "117") (name "unconnected-(OK9B-COL-Pad6)") (class "Default")
      (node (ref "OK9") (pin "6") (pinfunction "COL_6") (pintype "passive"))
    )
    (net (code "118") (name "unconnected-(OK9B-EMIT-Pad5)") (class "Default")
      (node (ref "OK9") (pin "5") (pinfunction "EMIT_5") (pintype "passive"))
    )
    (net (code "119") (name "unconnected-(U2-BOOT0-Pad44)") (class "Default")
      (node (ref "U2") (pin "44") (pinfunction "BOOT0_44") (pintype "input"))
    )
    (net (code "120") (name "unconnected-(U2-PA4-Pad14)") (class "Default")
      (node (ref "U2") (pin "14") (pinfunction "PA4_14") (pintype "bidirectional"))
    )
    (net (code "121") (name "unconnected-(U2-PA5-Pad15)") (class "Default")
      (node (ref "U2") (pin "15") (pinfunction "PA5_15") (pintype "bidirectional"))
    )
    (net (code "122") (name "unconnected-(U2-PA6-Pad16)") (class "Default")
      (node (ref "U2") (pin "16") (pinfunction "PA6_16") (pintype "bidirectional"))
    )
    (net (code "123") (name "unconnected-(U2-PA7-Pad17)") (class "Default")
      (node (ref "U2") (pin "17") (pinfunction "PA7_17") (pintype "bidirectional"))
    )
    (net (code "124") (name "unconnected-(U2-PA8-Pad29)") (class "Default")
      (node (ref "U2") (pin "29") (pinfunction "PA8_29") (pintype "bidirectional"))
    )
    (net (code "125") (name "unconnected-(U2-PA11-Pad32)") (class "Default")
      (node (ref "U2") (pin "32") (pinfunction "PA11_32") (pintype "bidirectional"))
    )
    (net (code "126") (name "unconnected-(U2-PA12-Pad33)") (class "Default")
      (node (ref "U2") (pin "33") (pinfunction "PA12_33") (pintype "bidirectional"))
    )
    (net (code "127") (name "unconnected-(U2-PB0-Pad18)") (class "Default")
      (node (ref "U2") (pin "18") (pinfunction "PB0_18") (pintype "bidirectional"))
    )
    (net (code "128") (name "unconnected-(U2-PB1-Pad19)") (class "Default")
      (node (ref "U2") (pin "19") (pinfunction "PB1_19") (pintype "bidirectional"))
    )
    (net (code "129") (name "unconnected-(U2-PB12-Pad25)") (class "Default")
      (node (ref "U2") (pin "25") (pinfunction "PB12_25") (pintype "bidirectional"))
    )
    (net (code "130") (name "unconnected-(U2-PB14-Pad27)") (class "Default")
      (node (ref "U2") (pin "27") (pinfunction "PB14_27") (pintype "bidirectional"))
    )
    (net (code "131") (name "unconnected-(U2-PC13-TAMPER-RTC-Pad2)") (class "Default")
      (node (ref "U2") (pin "2") (pinfunction "PC13-TAMPER-RTC_2") (pintype "bidirectional"))
    )
    (net (code "132") (name "unconnected-(U2-PC14-OSC32_IN-Pad3)") (class "Default")
      (node (ref "U2") (pin "3") (pinfunction "PC14-OSC32_IN_3") (pintype "bidirectional"))
    )
    (net (code "133") (name "unconnected-(U2-PC15-OSC32_OUT-Pad4)") (class "Default")
      (node (ref "U2") (pin "4") (pinfunction "PC15-OSC32_OUT_4") (pintype "bidirectional"))
    )
    (net (code "134") (name "unconnected-(U2-PD0-OSC_IN-Pad5)") (class "Default")
      (node (ref "U2") (pin "5") (pinfunction "PD0-OSC_IN_5") (pintype "input"))
    )
    (net (code "135") (name "unconnected-(U2-PD1-OSC_OUT-Pad6)") (class "Default")
      (node (ref "U2") (pin "6") (pinfunction "PD1-OSC_OUT_6") (pintype "output"))
    )
    (net (code "136") (name "unconnected-(X0-PA13{slash}SPI1_CS-Pad24)") (class "Default")
      (node (ref "X0") (pin "24") (pinfunction "PA13/SPI1_CS_24") (pintype "bidirectional"))
    )
    (net (code "137") (name "unconnected-(X0-PA14{slash}SPI1_CLK-Pad23)") (class "Default")
      (node (ref "X0") (pin "23") (pinfunction "PA14/SPI1_CLK_23") (pintype "bidirectional"))
    )
    (net (code "138") (name "unconnected-(X0-PA15{slash}SPI1_MOSI-Pad19)") (class "Default")
      (node (ref "X0") (pin "19") (pinfunction "PA15/SPI1_MOSI_19") (pintype "bidirectional"))
    )
    (net (code "139") (name "unconnected-(X0-PA16{slash}SPI1_MISO-Pad21)") (class "Default")
      (node (ref "X0") (pin "21") (pinfunction "PA16/SPI1_MISO_21") (pintype "bidirectional"))
    )
    (net (code "140") (name "unconnected-(X0-PA18{slash}TWI1_SCL-Pad18)") (class "Default")
      (node (ref "X0") (pin "18") (pinfunction "PA18/TWI1_SCL_18") (pintype "bidirectional"))
    )
    (net (code "141") (name "unconnected-(X0-PA19{slash}TWI1_SDA-Pad16)") (class "Default")
      (node (ref "X0") (pin "16") (pinfunction "PA19/TWI1_SDA_16") (pintype "bidirectional"))
    )
    (net (code "142") (name "unconnected-(X0-UART2_CTS{slash}PA03-Pad15)") (class "Default")
      (node (ref "X0") (pin "15") (pinfunction "UART2_CTS/PA03_15") (pintype "bidirectional"))
    )
    (net (code "143") (name "unconnected-(X0-UART2_RTS{slash}PA02-Pad22)") (class "Default")
      (node (ref "X0") (pin "22") (pinfunction "UART2_RTS/PA02_22") (pintype "bidirectional"))
    )
  )
)
